# hbridge.net
KiCad netlist of a schematic drawn in EAGLE
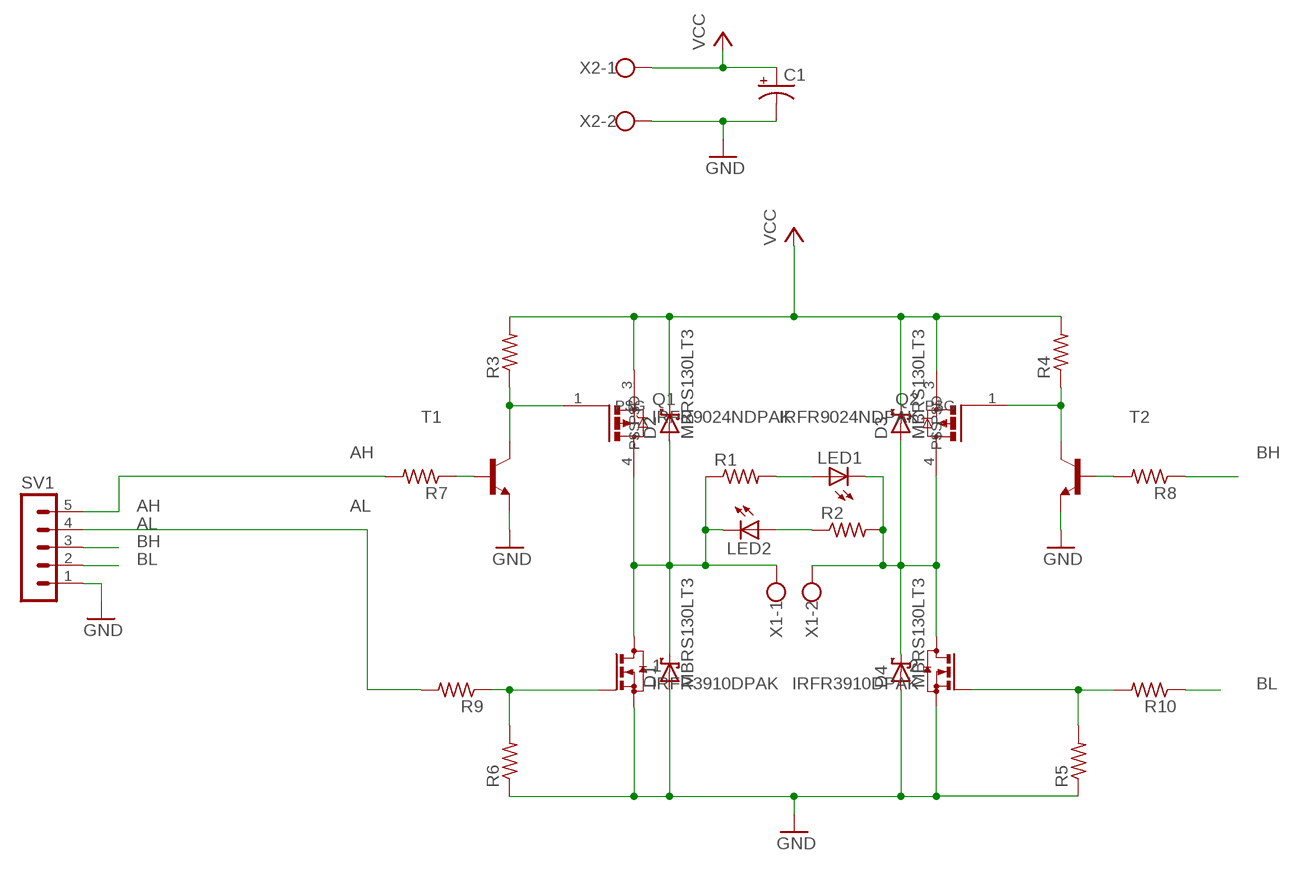
[diagram p0: schematic, sheet 1]

(export (version "E")
  (design (tool "Eeschema 10.0.6"))
  (components
    (comp (ref "1")
      (value "IRFR3910DPAK")
      (footprint "eagle-import:D-PAK_TO252AA")
      (libsource (lib "eagle-import") (part "IRFR3910DPAK"))
    )
    (comp (ref "2")
      (value "IRFR3910DPAK")
      (footprint "eagle-import:D-PAK_TO252AA")
      (libsource (lib "eagle-import") (part "IRFR3910DPAK"))
    )
    (comp (ref "C1")
      (value "CPOL-USE5-10.5")
      (footprint "eagle-import:E5-10,5")
      (libsource (lib "eagle-import") (part "CPOL-USE5-10.5"))
    )
    (comp (ref "D1")
      (value "MBRS130LT3")
      (footprint "eagle-import:SMB")
      (libsource (lib "eagle-import") (part "MBRS130LT3"))
    )
    (comp (ref "D2")
      (value "MBRS130LT3")
      (footprint "eagle-import:SMB")
      (libsource (lib "eagle-import") (part "MBRS130LT3"))
    )
    (comp (ref "D3")
      (value "MBRS130LT3")
      (footprint "eagle-import:SMB")
      (libsource (lib "eagle-import") (part "MBRS130LT3"))
    )
    (comp (ref "D4")
      (value "MBRS130LT3")
      (footprint "eagle-import:SMB")
      (libsource (lib "eagle-import") (part "MBRS130LT3"))
    )
    (comp (ref "LED1")
      (value "LEDCHIP-LED0805")
      (footprint "eagle-import:CHIP-LED0805")
      (libsource (lib "eagle-import") (part "LEDCHIP-LED0805"))
    )
    (comp (ref "LED2")
      (value "LEDCHIP-LED0805")
      (footprint "eagle-import:CHIP-LED0805")
      (libsource (lib "eagle-import") (part "LEDCHIP-LED0805"))
    )
    (comp (ref "Q1")
      (value "IRFR9024NDPAK")
      (footprint "eagle-import:D-PAK_TO252AA")
      (libsource (lib "eagle-import") (part "IRFR9024NDPAK"))
    )
    (comp (ref "Q2")
      (value "IRFR9024NDPAK")
      (footprint "eagle-import:D-PAK_TO252AA")
      (libsource (lib "eagle-import") (part "IRFR9024NDPAK"))
    )
    (comp (ref "R1")
      (value "R-US_R0805")
      (footprint "eagle-import:R0805")
      (libsource (lib "eagle-import") (part "R-US_R0805"))
    )
    (comp (ref "R2")
      (value "R-US_R0805")
      (footprint "eagle-import:R0805")
      (libsource (lib "eagle-import") (part "R-US_R0805"))
    )
    (comp (ref "R3")
      (value "R-US_R0805")
      (footprint "eagle-import:R0805")
      (libsource (lib "eagle-import") (part "R-US_R0805"))
    )
    (comp (ref "R4")
      (value "R-US_R0805")
      (footprint "eagle-import:R0805")
      (libsource (lib "eagle-import") (part "R-US_R0805"))
    )
    (comp (ref "R5")
      (value "R-US_R0805")
      (footprint "eagle-import:R0805")
      (libsource (lib "eagle-import") (part "R-US_R0805"))
    )
    (comp (ref "R6")
      (value "R-US_R0805")
      (footprint "eagle-import:R0805")
      (libsource (lib "eagle-import") (part "R-US_R0805"))
    )
    (comp (ref "R7")
      (value "R-US_R0805")
      (footprint "eagle-import:R0805")
      (libsource (lib "eagle-import") (part "R-US_R0805"))
    )
    (comp (ref "R8")
      (value "R-US_R0805")
      (footprint "eagle-import:R0805")
      (libsource (lib "eagle-import") (part "R-US_R0805"))
    )
    (comp (ref "R9")
      (value "R-US_R0805")
      (footprint "eagle-import:R0805")
      (libsource (lib "eagle-import") (part "R-US_R0805"))
    )
    (comp (ref "R10")
      (value "R-US_R0805")
      (footprint "eagle-import:R0805")
      (libsource (lib "eagle-import") (part "R-US_R0805"))
    )
    (comp (ref "SV1")
      (value "MA05-1")
      (footprint "eagle-import:MA05-1")
      (libsource (lib "eagle-import") (part "MA05-1"))
    )
    (comp (ref "T1")
      (value "MMBT2222ALT1-NPN-SOT23-BEC")
      (footprint "eagle-import:SOT23-BEC")
      (libsource (lib "eagle-import") (part "-NPN-SOT23-BECMMBT2222ALT1"))
    )
    (comp (ref "T2")
      (value "MMBT2222ALT1-NPN-SOT23-BEC")
      (footprint "eagle-import:SOT23-BEC")
      (libsource (lib "eagle-import") (part "-NPN-SOT23-BECMMBT2222ALT1"))
    )
    (comp (ref "X1")
      (value "W237-102")
      (footprint "eagle-import:W237-102")
      (fields (field (name "MPN") "237-102"))
      (libsource (lib "eagle-import") (part "W237-102"))
    )
    (comp (ref "X2")
      (value "W237-102")
      (footprint "eagle-import:W237-102")
      (fields
        (field (name "MPN") "237-102")
        (field (name "MPN_1") "237-102")
        (field (name "OC_FARNELL") "unknown")
        (field (name "OC_NEWARK") "70K9898")
      )
      (libsource (lib "eagle-import") (part "W237-102"))
    )
  )
  (nets
    (net (code "1") (name "/AH") (class "Default")
      (node (ref "R7") (pin "2") (pinfunction "2_2") (pintype "passive"))
      (node (ref "SV1") (pin "5") (pinfunction "5_5") (pintype "passive"))
    )
    (net (code "2") (name "/AL") (class "Default")
      (node (ref "R9") (pin "2") (pinfunction "2_2") (pintype "passive"))
      (node (ref "SV1") (pin "4") (pinfunction "4_4") (pintype "passive"))
    )
    (net (code "3") (name "/BH") (class "Default")
      (node (ref "R8") (pin "1") (pinfunction "1_1") (pintype "passive"))
      (node (ref "SV1") (pin "3") (pinfunction "3_3") (pintype "passive"))
    )
    (net (code "4") (name "/BL") (class "Default")
      (node (ref "R10") (pin "1") (pinfunction "1_1") (pintype "passive"))
      (node (ref "SV1") (pin "2") (pinfunction "2_2") (pintype "passive"))
    )
    (net (code "5") (name "GND") (class "Default")
      (node (ref "1") (pin "3") (pinfunction "S_3") (pintype "passive"))
      (node (ref "2") (pin "3") (pinfunction "S_3") (pintype "passive"))
      (node (ref "C1") (pin "-") (pinfunction "-_-") (pintype "passive"))
      (node (ref "D1") (pin "A") (pinfunction "A_A") (pintype "passive"))
      (node (ref "D4") (pin "A") (pinfunction "A_A") (pintype "passive"))
      (node (ref "R5") (pin "1") (pinfunction "1_1") (pintype "passive"))
      (node (ref "R6") (pin "1") (pinfunction "1_1") (pintype "passive"))
      (node (ref "SV1") (pin "1") (pinfunction "1_1") (pintype "passive"))
      (node (ref "T1") (pin "E") (pinfunction "E_E") (pintype "passive"))
      (node (ref "T2") (pin "E") (pinfunction "E_E") (pintype "passive"))
      (node (ref "X2") (pin "2") (pinfunction "KL_2") (pintype "passive"))
    )
    (net (code "6") (name "Net-(1-D)") (class "Default")
      (node (ref "1") (pin "4") (pinfunction "D_4") (pintype "passive"))
      (node (ref "D1") (pin "C") (pinfunction "C_C") (pintype "passive"))
      (node (ref "D2") (pin "A") (pinfunction "A_A") (pintype "passive"))
      (node (ref "LED2") (pin "C") (pinfunction "C_C") (pintype "passive"))
      (node (ref "Q1") (pin "4") (pinfunction "P$D_4") (pintype "bidirectional"))
      (node (ref "R1") (pin "1") (pinfunction "1_1") (pintype "passive"))
      (node (ref "X1") (pin "1") (pinfunction "KL_1") (pintype "passive"))
    )
    (net (code "7") (name "Net-(1-G)") (class "Default")
      (node (ref "1") (pin "1") (pinfunction "G_1") (pintype "passive"))
      (node (ref "R6") (pin "2") (pinfunction "2_2") (pintype "passive"))
      (node (ref "R9") (pin "1") (pinfunction "1_1") (pintype "passive"))
    )
    (net (code "8") (name "Net-(2-D)") (class "Default")
      (node (ref "2") (pin "4") (pinfunction "D_4") (pintype "passive"))
      (node (ref "D3") (pin "A") (pinfunction "A_A") (pintype "passive"))
      (node (ref "D4") (pin "C") (pinfunction "C_C") (pintype "passive"))
      (node (ref "LED1") (pin "C") (pinfunction "C_C") (pintype "passive"))
      (node (ref "Q2") (pin "4") (pinfunction "P$D_4") (pintype "bidirectional"))
      (node (ref "R2") (pin "2") (pinfunction "2_2") (pintype "passive"))
      (node (ref "X1") (pin "2") (pinfunction "KL_2") (pintype "passive"))
    )
    (net (code "9") (name "Net-(2-G)") (class "Default")
      (node (ref "2") (pin "1") (pinfunction "G_1") (pintype "passive"))
      (node (ref "R10") (pin "2") (pinfunction "2_2") (pintype "passive"))
      (node (ref "R5") (pin "2") (pinfunction "2_2") (pintype "passive"))
    )
    (net (code "10") (name "Net-(LED1-PadA)") (class "Default")
      (node (ref "LED1") (pin "A") (pinfunction "A_A") (pintype "passive"))
      (node (ref "R1") (pin "2") (pinfunction "2_2") (pintype "passive"))
    )
    (net (code "11") (name "Net-(LED2-PadA)") (class "Default")
      (node (ref "LED2") (pin "A") (pinfunction "A_A") (pintype "passive"))
      (node (ref "R2") (pin "1") (pinfunction "1_1") (pintype "passive"))
    )
    (net (code "12") (name "Net-(Q1-P$G)") (class "Default")
      (node (ref "Q1") (pin "1") (pinfunction "P$G_1") (pintype "bidirectional"))
      (node (ref "R3") (pin "1") (pinfunction "1_1") (pintype "passive"))
      (node (ref "T1") (pin "C") (pinfunction "C_C") (pintype "passive"))
    )
    (net (code "13") (name "Net-(Q2-P$G)") (class "Default")
      (node (ref "Q2") (pin "1") (pinfunction "P$G_1") (pintype "bidirectional"))
      (node (ref "R4") (pin "1") (pinfunction "1_1") (pintype "passive"))
      (node (ref "T2") (pin "C") (pinfunction "C_C") (pintype "passive"))
    )
    (net (code "14") (name "Net-(R7-Pad1)") (class "Default")
      (node (ref "R7") (pin "1") (pinfunction "1_1") (pintype "passive"))
      (node (ref "T1") (pin "B") (pinfunction "B_B") (pintype "passive"))
    )
    (net (code "15") (name "Net-(R8-Pad2)") (class "Default")
      (node (ref "R8") (pin "2") (pinfunction "2_2") (pintype "passive"))
      (node (ref "T2") (pin "B") (pinfunction "B_B") (pintype "passive"))
    )
    (net (code "16") (name "VCC") (class "Default")
      (node (ref "C1") (pin "+") (pinfunction "+_+") (pintype "passive"))
      (node (ref "D2") (pin "C") (pinfunction "C_C") (pintype "passive"))
      (node (ref "D3") (pin "C") (pinfunction "C_C") (pintype "passive"))
      (node (ref "Q1") (pin "3") (pinfunction "P$S_3") (pintype "bidirectional"))
      (node (ref "Q2") (pin "3") (pinfunction "P$S_3") (pintype "bidirectional"))
      (node (ref "R3") (pin "2") (pinfunction "2_2") (pintype "passive"))
      (node (ref "R4") (pin "2") (pinfunction "2_2") (pintype "passive"))
      (node (ref "X2") (pin "1") (pinfunction "KL_1") (pintype "passive"))
    )
  )
)
